# 03_Power.net
KiCad netlist of a schematic drawn in Altium Designer
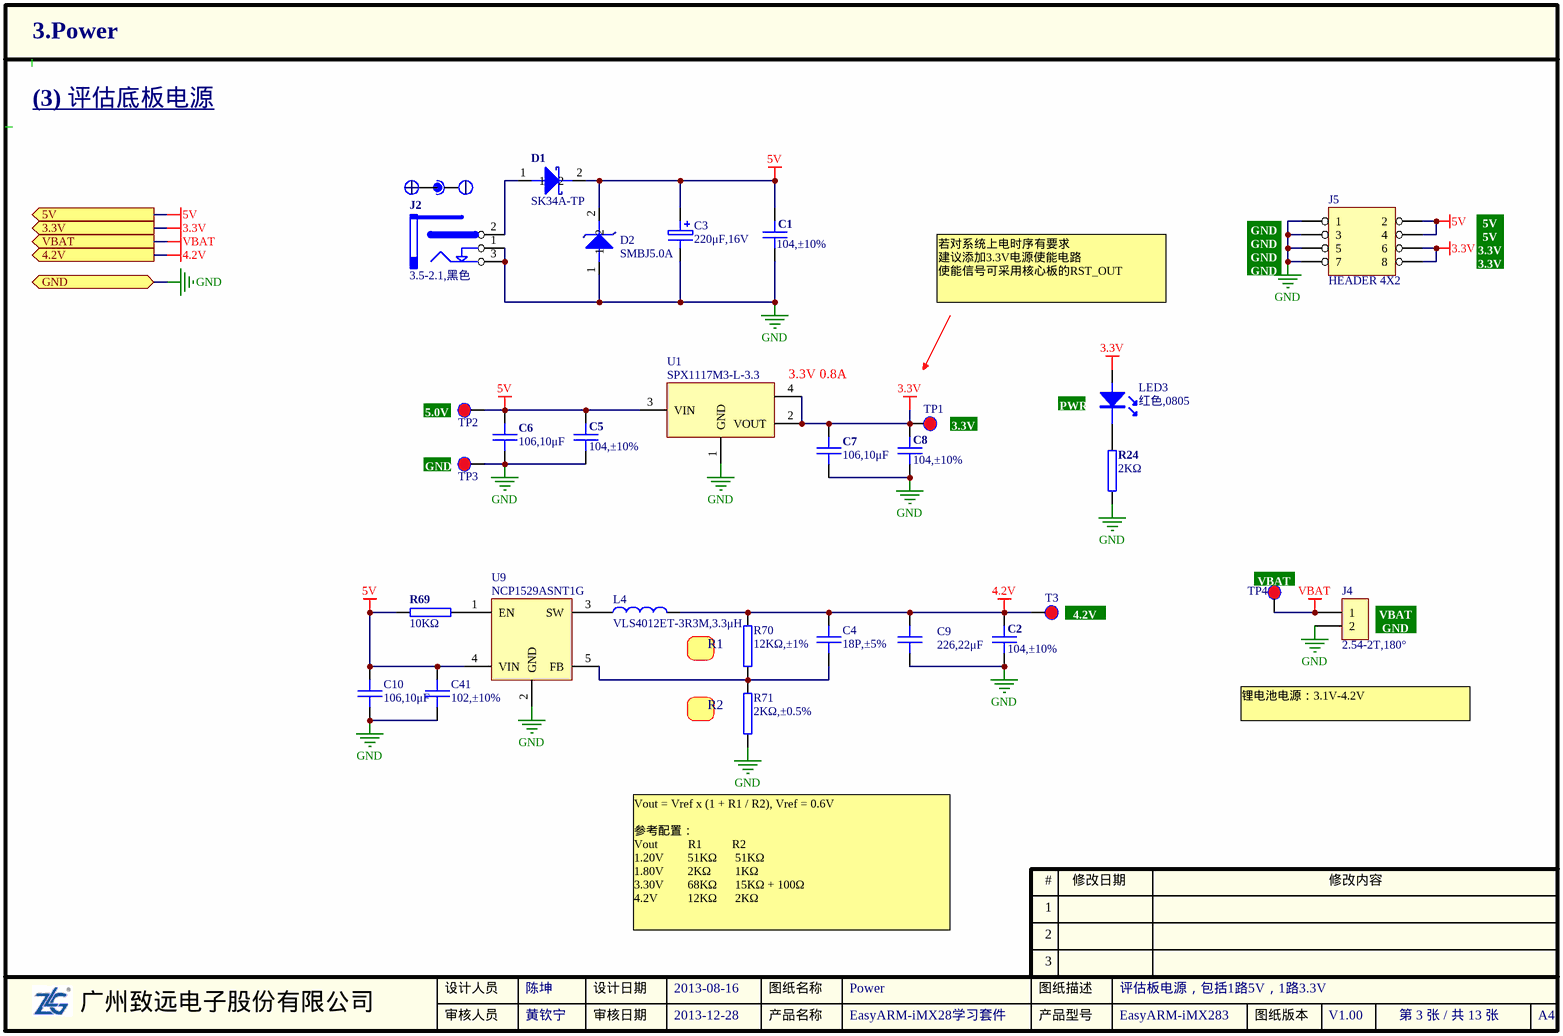
[diagram p0: 03. Power.SchDoc]

(export (version "E")
  (design (tool "Eeschema 10.0.6"))
  (components
    (comp (ref "C1")
      (value "104,±10%")
      (footprint "0603C")
      (description "104,±10%,50V,X7R,0603,*,RoHS")
      (libsource (lib "ErpMaterialData") (part "CAP1"))
    )
    (comp (ref "C2")
      (value "104,±10%")
      (footprint "0603C")
      (description "104,±10%,50V,X7R,0603,*,RoHS")
      (libsource (lib "ErpMaterialData") (part "CAP1"))
    )
    (comp (ref "C3")
      (value "220μF,16V")
      (footprint "RB-.1/.25")
      (description "220μF,16V,Ф6.3×7mm,,珠海华冠,RoHS")
      (libsource (lib "ErpMaterialData") (part "CAP ELECTRO1"))
    )
    (comp (ref "C4")
      (value "18P,±5%")
      (footprint "0603C")
      (description "18P,±5%,50V,COG,0603,*,RoHS")
      (libsource (lib "ErpMaterialData") (part "CAP1"))
    )
    (comp (ref "C5")
      (value "104,±10%")
      (footprint "0603C")
      (description "104,±10%,50V,X7R,0603,*,RoHS")
      (libsource (lib "ErpMaterialData") (part "CAP1"))
    )
    (comp (ref "C6")
      (value "106,10μF")
      (footprint "0805C")
      (description "106,10μF,±10%,10V,X5R,0805,RoHS")
      (libsource (lib "ErpMaterialData") (part "CAP1"))
    )
    (comp (ref "C7")
      (value "106,10μF")
      (footprint "0805C")
      (description "106,10μF,±10%,10V,X5R,0805,RoHS")
      (libsource (lib "ErpMaterialData") (part "CAP1"))
    )
    (comp (ref "C8")
      (value "104,±10%")
      (footprint "0603C")
      (description "104,±10%,50V,X7R,0603,*,RoHS")
      (libsource (lib "ErpMaterialData") (part "CAP1"))
    )
    (comp (ref "C9")
      (value "226,22μF")
      (footprint "0805C")
      (description "226,22μF,±20%,6.3V,X5R,0805,RoHS")
      (libsource (lib "ErpMaterialData") (part "CAP1"))
    )
    (comp (ref "C10")
      (value "106,10μF")
      (footprint "0805C")
      (description "106,10μF,±10%,10V,X5R,0805,RoHS")
      (libsource (lib "ErpMaterialData") (part "CAP1"))
    )
    (comp (ref "C41")
      (value "102,±10%")
      (footprint "0603C")
      (description "102,±10%,50V,X7R,0603,*,RoHS")
      (libsource (lib "ErpMaterialData") (part "CAP1"))
    )
    (comp (ref "D1")
      (value "SK34A-TP")
      (footprint "SOD-SK34A")
      (description "SK34A-TP,DO-214AC,MCC,RoHS")
      (fields (field (name "Comment") "DIODE SCHOTTKY"))
      (libsource (lib "ErpMaterialData") (part "DIODE SCHOTTKY"))
    )
    (comp (ref "D2")
      (value "SMBJ5.0A")
      (footprint "1812D")
      (description "SMBJ5.0A,DO-214AA,君耀,RoHS")
      (fields (field (name "Comment") "DIODE ZENER"))
      (libsource (lib "ErpMaterialData") (part "DIODE ZENER"))
    )
    (comp (ref "J2")
      (value "3.5-2.1,黑色")
      (footprint "POWER-AC")
      (description "3.5-2.1,黑色,RoHS")
      (fields (field (name "Comment") "POWER-COM"))
      (libsource (lib "ErpMaterialData") (part "POWER-COM"))
    )
    (comp (ref "J4")
      (value "2.54-2T,180°")
      (footprint "CN-2-2.54")
      (description "2.54-2T,180°,,*")
      (fields (field (name "Comment") "CON2"))
      (libsource (lib "ErpMaterialData") (part "CON2"))
    )
    (comp (ref "J5") (value "HEADER 4X2") (footprint "IDC-8") (libsource (lib "无需物料号元件") (part "HEADER 4X2")))
    (comp (ref "L4")
      (value "VLS4012ET-3R3M,3.3μH")
      (footprint "L-4.0S-VLS")
      (description "VLS4012ET-3R3M,3.3μH,1.4A,SMD,TDK,RoHS")
      (fields (field (name "Comment") "INDUCTOR1"))
      (libsource (lib "ErpMaterialData") (part "INDUCTOR1"))
    )
    (comp (ref "LED3")
      (value "红色,0805")
      (footprint "LED-0805")
      (description "红色,0805,0805,RoHS")
      (fields (field (name "Comment") "LED1"))
      (libsource (lib "ErpMaterialData") (part "LED1"))
    )
    (comp (ref "R24")
      (value "2KΩ")
      (footprint "0603R")
      (description "2KΩ,0603,*,RoHS")
      (libsource (lib "ErpMaterialData") (part "RES2"))
    )
    (comp (ref "R69")
      (value "10KΩ")
      (footprint "0603R")
      (description "10KΩ,0603,*,RoHS")
      (libsource (lib "ErpMaterialData") (part "RES2"))
    )
    (comp (ref "R70")
      (value "12KΩ,±1%")
      (footprint "0603R")
      (description "12KΩ,±1%,0603,*,RoHS")
      (libsource (lib "ErpMaterialData") (part "RES2"))
    )
    (comp (ref "R71")
      (value "2KΩ,±0.5%")
      (footprint "0603R")
      (description "2KΩ,±0.5%,0603,*,RoHS")
      (libsource (lib "ErpMaterialData") (part "RES2"))
    )
    (comp (ref "T3") (value "4.2V") (footprint "PAD-40") (libsource (lib "无需物料号元件") (part "TEST-DOT")))
    (comp (ref "TP1") (value "3.3V") (footprint "PAD-40") (libsource (lib "无需物料号元件") (part "TEST-DOT")))
    (comp (ref "TP2") (value "5.0V") (footprint "PAD-40") (libsource (lib "无需物料号元件") (part "TEST-DOT")))
    (comp (ref "TP3") (value "GND") (footprint "PAD-40") (libsource (lib "无需物料号元件") (part "TEST-DOT")))
    (comp (ref "TP4") (value "VBAT") (footprint "PAD-40") (libsource (lib "无需物料号元件") (part "TEST-DOT")))
    (comp (ref "U1")
      (value "SPX1117M3-L-3.3")
      (footprint "SOT-223")
      (description "SPX1117M3-L-3.3,SOT-223,EXAR,RoHS")
      (fields (field (name "Comment") "SPX1117M3-L/TR"))
      (libsource (lib "ErpMaterialData") (part "SPX1117M3"))
    )
    (comp (ref "U9")
      (value "NCP1529ASNT1G")
      (footprint "SOT-23-5")
      (description "NCP1529ASNT1G,TSOP-5,ON,RoHS")
      (fields (field (name "Comment") "SCY99090SNT1G"))
      (libsource (lib "ErpMaterialData") (part "SCY99090SNT1G"))
    )
  )
  (nets
    (net (code "1") (name "3.3V") (class "Default")
      (node (ref "C7") (pin "1") (pinfunction "1_1") (pintype "passive"))
      (node (ref "C8") (pin "1") (pinfunction "1_1") (pintype "passive"))
      (node (ref "J5") (pin "6") (pinfunction "6_6") (pintype "passive"))
      (node (ref "J5") (pin "8") (pinfunction "8_8") (pintype "passive"))
      (node (ref "LED3") (pin "1") (pinfunction "1_1") (pintype "passive"))
      (node (ref "TP1") (pin "1") (pinfunction "1_1") (pintype "passive"))
      (node (ref "U1") (pin "2") (pinfunction "VOUT_2") (pintype "passive"))
      (node (ref "U1") (pin "4") (pintype "passive"))
    )
    (net (code "2") (name "4.2V") (class "Default")
      (node (ref "C2") (pin "1") (pinfunction "1_1") (pintype "passive"))
      (node (ref "C4") (pin "1") (pinfunction "1_1") (pintype "passive"))
      (node (ref "C9") (pin "1") (pinfunction "1_1") (pintype "passive"))
      (node (ref "L4") (pin "2") (pinfunction "2_2") (pintype "passive"))
      (node (ref "R70") (pin "2") (pinfunction "2_2") (pintype "passive"))
      (node (ref "T3") (pin "1") (pinfunction "1_1") (pintype "passive"))
    )
    (net (code "3") (name "5V") (class "Default")
      (node (ref "C1") (pin "1") (pinfunction "1_1") (pintype "passive"))
      (node (ref "C10") (pin "1") (pinfunction "1_1") (pintype "passive"))
      (node (ref "C3") (pin "1") (pinfunction "1_1") (pintype "passive"))
      (node (ref "C41") (pin "1") (pinfunction "1_1") (pintype "passive"))
      (node (ref "C5") (pin "1") (pinfunction "1_1") (pintype "passive"))
      (node (ref "C6") (pin "1") (pinfunction "1_1") (pintype "passive"))
      (node (ref "D1") (pin "2") (pinfunction "2_2") (pintype "passive"))
      (node (ref "D2") (pin "2") (pinfunction "2_2") (pintype "passive"))
      (node (ref "J5") (pin "2") (pinfunction "2_2") (pintype "passive"))
      (node (ref "J5") (pin "4") (pinfunction "4_4") (pintype "passive"))
      (node (ref "R69") (pin "1") (pinfunction "1_1") (pintype "passive"))
      (node (ref "TP2") (pin "1") (pinfunction "1_1") (pintype "passive"))
      (node (ref "U1") (pin "3") (pinfunction "VIN_3") (pintype "passive"))
      (node (ref "U9") (pin "4") (pinfunction "VIN_4") (pintype "passive"))
    )
    (net (code "4") (name "GND") (class "Default")
      (node (ref "C1") (pin "2") (pinfunction "2_2") (pintype "passive"))
      (node (ref "C10") (pin "2") (pinfunction "2_2") (pintype "passive"))
      (node (ref "C2") (pin "2") (pinfunction "2_2") (pintype "passive"))
      (node (ref "C3") (pin "2") (pinfunction "2_2") (pintype "passive"))
      (node (ref "C41") (pin "2") (pinfunction "2_2") (pintype "passive"))
      (node (ref "C5") (pin "2") (pinfunction "2_2") (pintype "passive"))
      (node (ref "C6") (pin "2") (pinfunction "2_2") (pintype "passive"))
      (node (ref "C7") (pin "2") (pinfunction "2_2") (pintype "passive"))
      (node (ref "C8") (pin "2") (pinfunction "2_2") (pintype "passive"))
      (node (ref "C9") (pin "2") (pinfunction "2_2") (pintype "passive"))
      (node (ref "D2") (pin "1") (pinfunction "1_1") (pintype "passive"))
      (node (ref "J2") (pin "1") (pinfunction "A_1") (pintype "passive"))
      (node (ref "J2") (pin "3") (pinfunction "B_3") (pintype "passive"))
      (node (ref "J4") (pin "2") (pinfunction "2_2") (pintype "passive"))
      (node (ref "J5") (pin "1") (pinfunction "1_1") (pintype "passive"))
      (node (ref "J5") (pin "3") (pinfunction "3_3") (pintype "passive"))
      (node (ref "J5") (pin "5") (pinfunction "5_5") (pintype "passive"))
      (node (ref "J5") (pin "7") (pinfunction "7_7") (pintype "passive"))
      (node (ref "R24") (pin "1") (pinfunction "1_1") (pintype "passive"))
      (node (ref "R71") (pin "1") (pinfunction "1_1") (pintype "passive"))
      (node (ref "TP3") (pin "1") (pinfunction "1_1") (pintype "passive"))
      (node (ref "U1") (pin "1") (pinfunction "GND_1") (pintype "passive"))
      (node (ref "U9") (pin "2") (pinfunction "GND_2") (pintype "passive"))
    )
    (net (code "5") (name "Net-(D1-Pad1)") (class "Default")
      (node (ref "D1") (pin "1") (pinfunction "1_1") (pintype "passive"))
      (node (ref "J2") (pin "2") (pinfunction "B_2") (pintype "passive"))
    )
    (net (code "6") (name "Net-(LED3-Pad2)") (class "Default")
      (node (ref "LED3") (pin "2") (pinfunction "2_2") (pintype "passive"))
      (node (ref "R24") (pin "2") (pinfunction "2_2") (pintype "passive"))
    )
    (net (code "7") (name "Net-(U9-EN)") (class "Default")
      (node (ref "R69") (pin "2") (pinfunction "2_2") (pintype "passive"))
      (node (ref "U9") (pin "1") (pinfunction "EN_1") (pintype "passive"))
    )
    (net (code "8") (name "Net-(U9-FB)") (class "Default")
      (node (ref "C4") (pin "2") (pinfunction "2_2") (pintype "passive"))
      (node (ref "R70") (pin "1") (pinfunction "1_1") (pintype "passive"))
      (node (ref "R71") (pin "2") (pinfunction "2_2") (pintype "passive"))
      (node (ref "U9") (pin "5") (pinfunction "FB_5") (pintype "passive"))
    )
    (net (code "9") (name "Net-(U9-SW)") (class "Default")
      (node (ref "L4") (pin "1") (pinfunction "1_1") (pintype "passive"))
      (node (ref "U9") (pin "3") (pinfunction "SW_3") (pintype "passive"))
    )
    (net (code "10") (name "VBAT") (class "Default")
      (node (ref "J4") (pin "1") (pinfunction "1_1") (pintype "passive"))
      (node (ref "TP4") (pin "1") (pinfunction "1_1") (pintype "passive"))
    )
  )
)
